# usd.net
KiCad netlist of a schematic drawn in Altium Designer
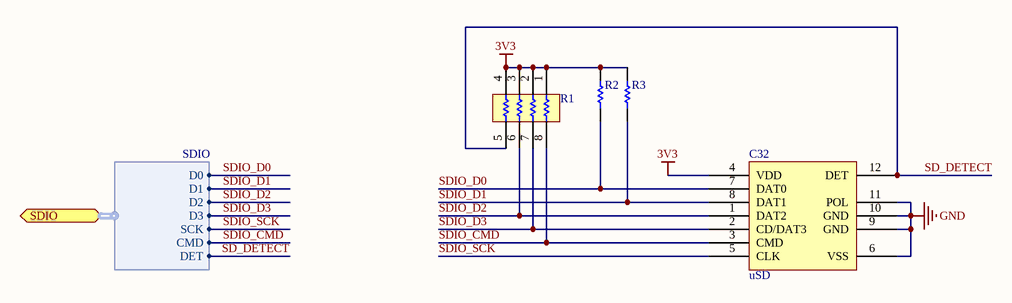
[diagram p0: usd.SchDoc]

(export (version "E")
  (design (tool "Eeschema 10.0.6"))
  (components
    (comp (ref "C32")
      (value "uSD")
      (footprint "47309-XXX 3.35mm")
      (description "molex MICROSD/MICROSIM Connector")
      (libsource (lib "molex") (part "47309-XXX"))
    )
    (comp (ref "R1")
      (value "CAY16-103J4LF")
      (footprint "BOUR-CAY16-J4_V")
      (description "Chip Resistor Array, 10 KOhm, +/- 5%, 62.5 mW, -55 to 125 degC, 8-Pin SMD, RoHS, Tape and Reel")
      (fields (field (name "TOLERANCE") "1%"))
      (libsource (lib "Altium Content Vault") (part "CMP-1747-00005-1"))
    )
    (comp (ref "R2")
      (value "47K 5% 0402(1005)")
      (footprint "RESC0402(1005)_M")
      (description "47K 0.063W 5% 0402 (1005 Metric)  SMD")
      (fields (field (name "TOLERANCE") "5 %") (field (name "POWER") "0.063 W"))
      (libsource (lib "Altium Content Vault") (part "RES"))
    )
    (comp (ref "R3")
      (value "47K 5% 0402(1005)")
      (footprint "RESC0402(1005)_M")
      (description "47K 0.063W 5% 0402 (1005 Metric)  SMD")
      (fields (field (name "TOLERANCE") "5 %") (field (name "POWER") "0.063 W"))
      (libsource (lib "Altium Content Vault") (part "CMP-1011-00114-1"))
    )
  )
  (nets
    (net (code "2") (name "/SDIO_CMD") (class "Default")
      (node (ref "C32") (pin "3") (pinfunction "CMD_3") (pintype "passive"))
      (node (ref "R1") (pin "8") (pinfunction "8_8") (pintype "passive"))
    )
    (net (code "3") (name "/SDIO_D0") (class "Default")
      (node (ref "C32") (pin "7") (pinfunction "DAT0_7") (pintype "passive"))
      (node (ref "R2") (pin "1") (pinfunction "1_1") (pintype "passive"))
    )
    (net (code "4") (name "/SDIO_D1") (class "Default")
      (node (ref "C32") (pin "8") (pinfunction "DAT1_8") (pintype "passive"))
      (node (ref "R3") (pin "1") (pinfunction "1_1") (pintype "passive"))
    )
    (net (code "5") (name "/SDIO_D2") (class "Default")
      (node (ref "C32") (pin "1") (pinfunction "DAT2_1") (pintype "passive"))
      (node (ref "R1") (pin "6") (pinfunction "6_6") (pintype "passive"))
    )
    (net (code "6") (name "/SDIO_D3") (class "Default")
      (node (ref "C32") (pin "2") (pinfunction "CD/DAT3_2") (pintype "passive"))
      (node (ref "R1") (pin "7") (pinfunction "7_7") (pintype "passive"))
    )
    (net (code "7") (name "/SDIO_SCK") (class "Default")
      (node (ref "C32") (pin "5") (pinfunction "CLK_5") (pintype "passive"))
    )
    (net (code "8") (name "/SD_DETECT") (class "Default")
      (node (ref "C32") (pin "12") (pinfunction "DET_12") (pintype "passive"))
      (node (ref "R1") (pin "5") (pinfunction "5_5") (pintype "passive"))
    )
    (net (code "10") (name "3V3") (class "Default")
      (node (ref "C32") (pin "4") (pinfunction "VDD_4") (pintype "passive"))
      (node (ref "R1") (pin "1") (pinfunction "1_1") (pintype "passive"))
      (node (ref "R1") (pin "2") (pinfunction "2_2") (pintype "passive"))
      (node (ref "R1") (pin "3") (pinfunction "3_3") (pintype "passive"))
      (node (ref "R1") (pin "4") (pinfunction "4_4") (pintype "passive"))
      (node (ref "R2") (pin "2") (pinfunction "2_2") (pintype "passive"))
      (node (ref "R3") (pin "2") (pinfunction "2_2") (pintype "passive"))
    )
    (net (code "11") (name "GND") (class "Default")
      (node (ref "C32") (pin "10") (pinfunction "GND_10") (pintype "passive"))
      (node (ref "C32") (pin "11") (pinfunction "POL_11") (pintype "passive"))
      (node (ref "C32") (pin "6") (pinfunction "VSS_6") (pintype "passive"))
      (node (ref "C32") (pin "9") (pinfunction "GND_9") (pintype "passive"))
    )
  )
)
